# Sheet2.net
KiCad netlist of a schematic drawn in Altium Designer
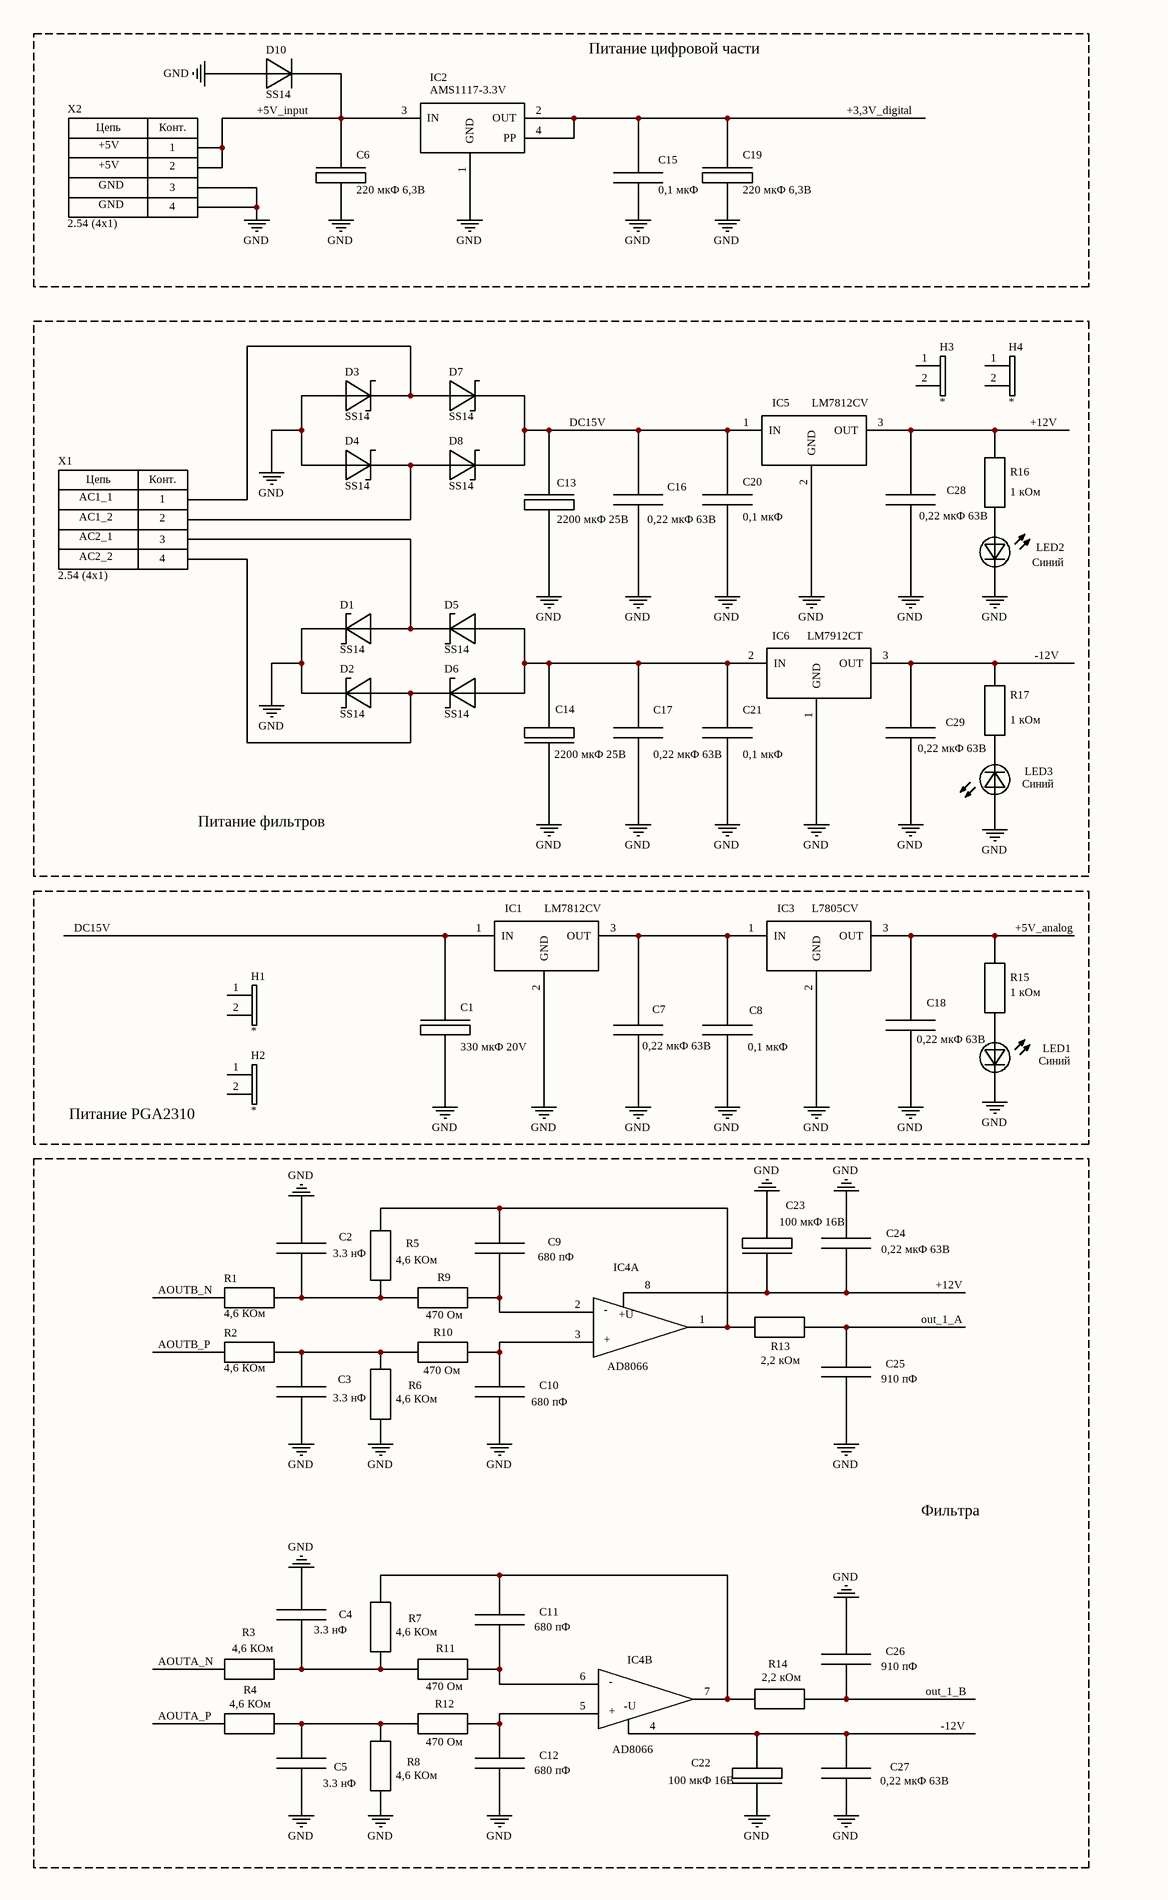
[diagram p0: Sheet2.SchDoc, left]
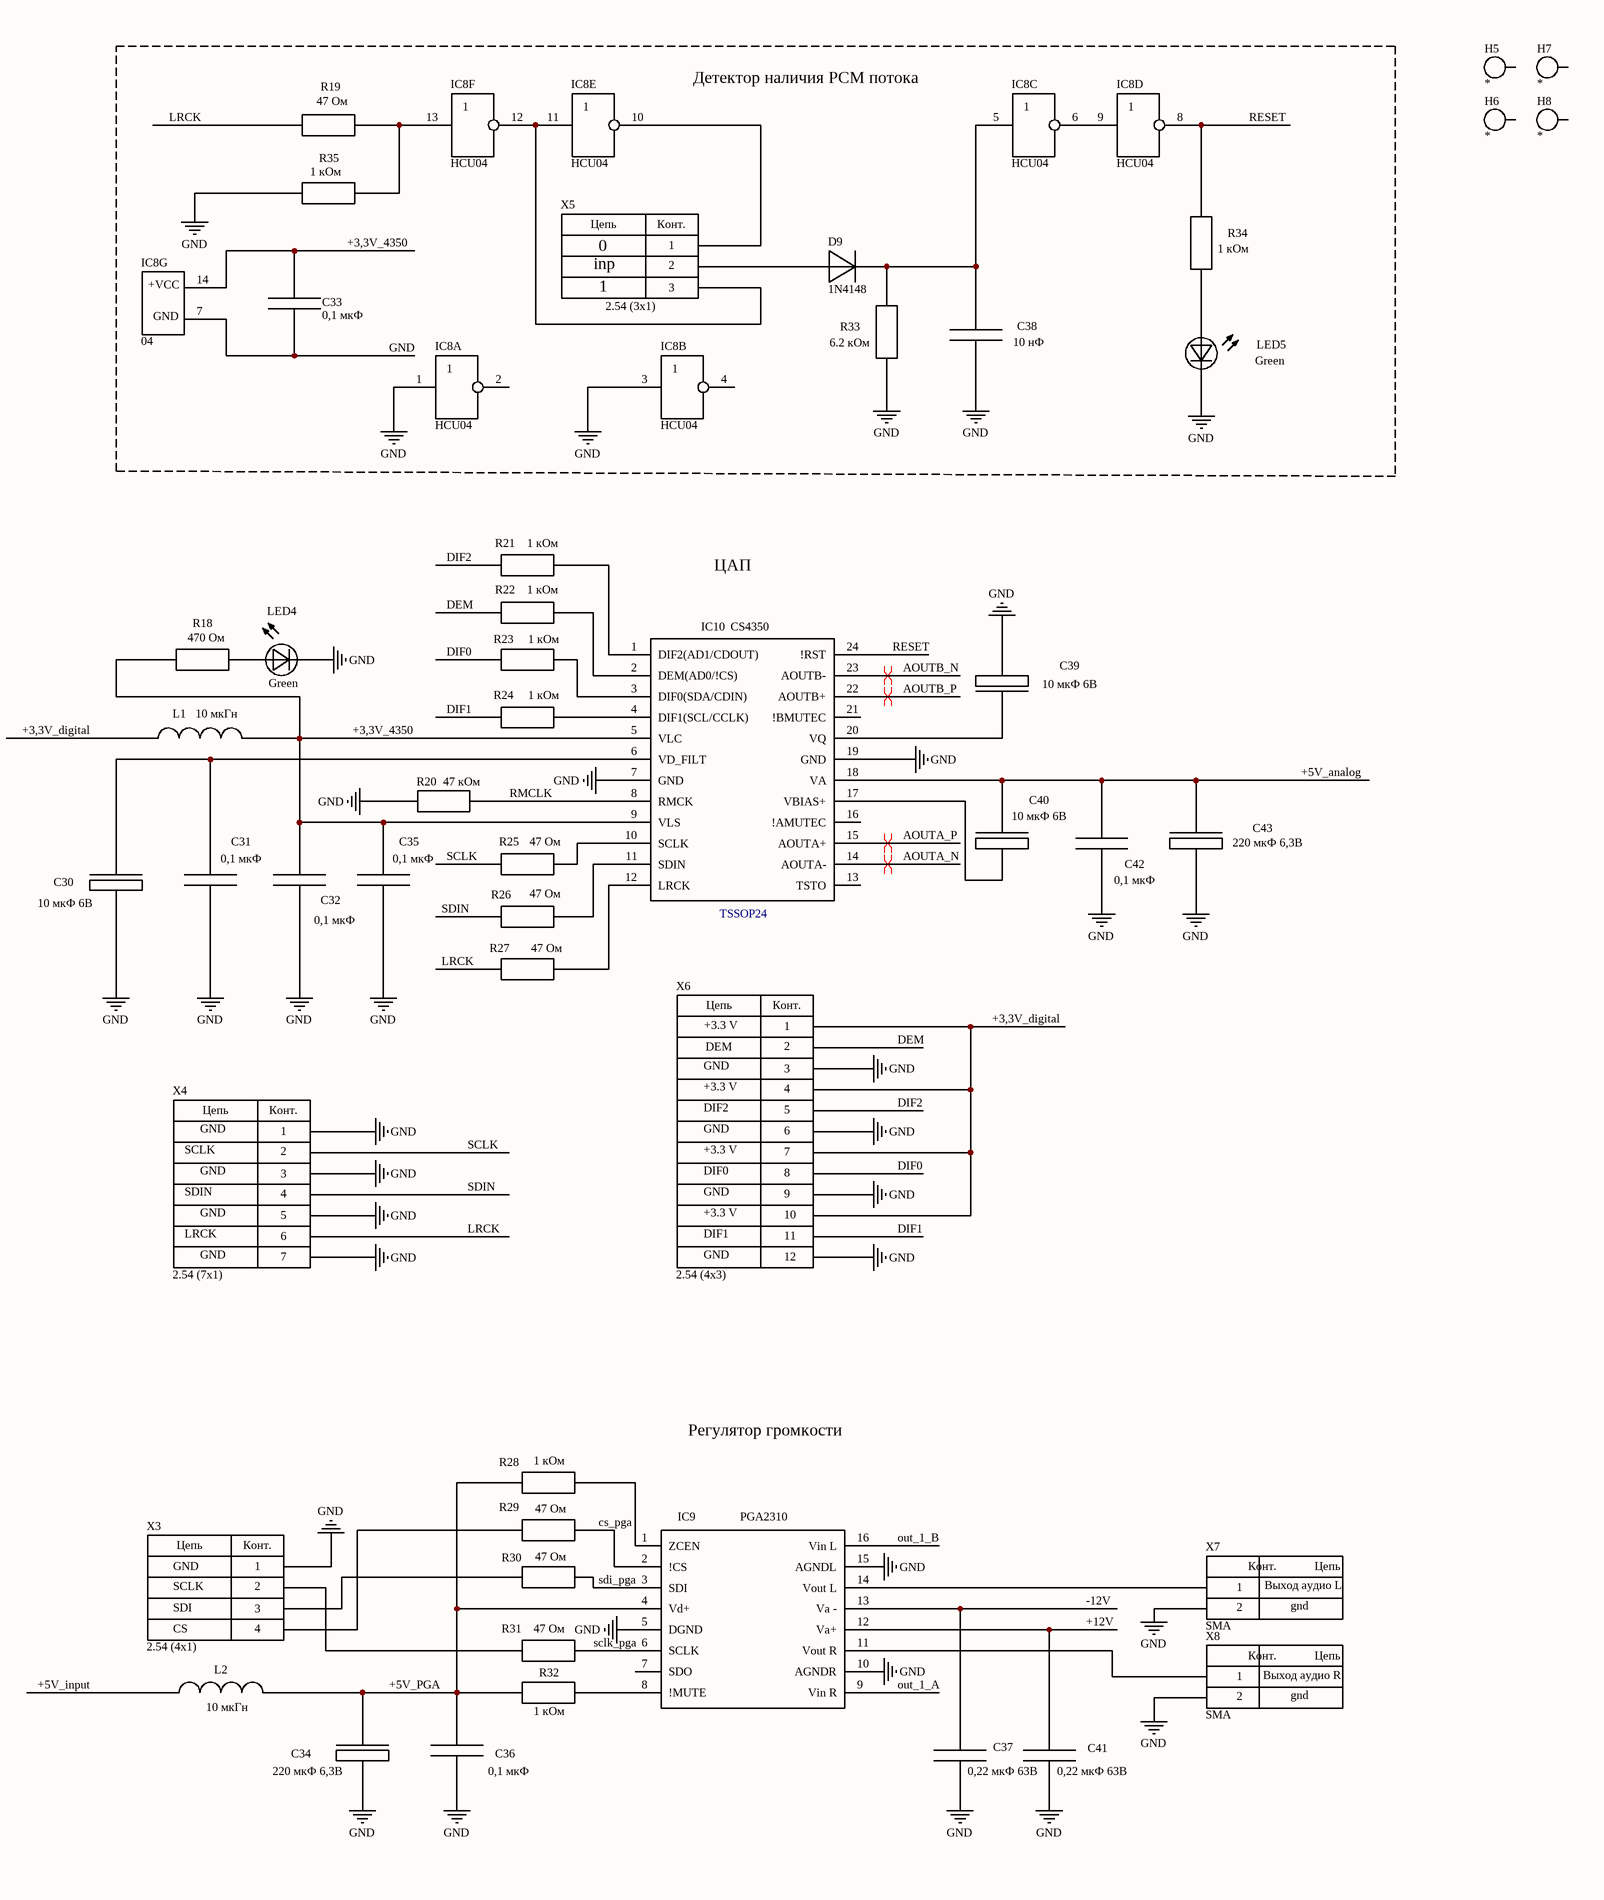
[diagram p1: Sheet2.SchDoc, right]

(export (version "E")
  (design (tool "Eeschema 10.0.6"))
  (components
    (comp (ref "C1")
      (value "330 мкФ 20V")
      (footprint "Конденсатор D=8 H=11.5")
      (libsource (lib "") (part "Конденсатор_1"))
    )
    (comp (ref "C2")
      (value "3.3 нФ")
      (footprint "Конденсатор WIMA 4.5x7x5")
      (libsource (lib "S83") (part "Конденсатор"))
    )
    (comp (ref "C3")
      (value "3.3 нФ")
      (footprint "Конденсатор WIMA 4.5x7x5")
      (libsource (lib "S83") (part "Конденсатор"))
    )
    (comp (ref "C4")
      (value "3.3 нФ")
      (footprint "Конденсатор WIMA 4.5x7x5")
      (libsource (lib "S83") (part "Конденсатор"))
    )
    (comp (ref "C5")
      (value "3.3 нФ")
      (footprint "Конденсатор WIMA 4.5x7x5")
      (libsource (lib "S83") (part "Конденсатор"))
    )
    (comp (ref "C6")
      (value "220 мкФ 6,3В")
      (footprint "Конденсатор SMD Case Size D")
      (libsource (lib "") (part "Конденсатор_1"))
    )
    (comp (ref "C7")
      (value "0,22 мкФ 63В")
      (footprint "Конденсатор WIMA 3x7x7")
      (libsource (lib "S83") (part "Конденсатор"))
    )
    (comp (ref "C8")
      (value "0,1 мкФ")
      (footprint "Конденсатор SMD Case 1206")
      (libsource (lib "S83") (part "Конденсатор"))
    )
    (comp (ref "C9")
      (value "680 пФ")
      (footprint "Конденсатор WIMA 4.5x7x5")
      (libsource (lib "S83") (part "Конденсатор"))
    )
    (comp (ref "C10")
      (value "680 пФ")
      (footprint "Конденсатор WIMA 4.5x7x5")
      (libsource (lib "S83") (part "Конденсатор"))
    )
    (comp (ref "C11")
      (value "680 пФ")
      (footprint "Конденсатор WIMA 4.5x7x5")
      (libsource (lib "S83") (part "Конденсатор"))
    )
    (comp (ref "C12")
      (value "680 пФ")
      (footprint "Конденсатор WIMA 4.5x7x5")
      (libsource (lib "S83") (part "Конденсатор"))
    )
    (comp (ref "C13")
      (value "2200 мкФ 25В")
      (footprint "Конденсатор D=13 H=25")
      (libsource (lib "") (part "Конденсатор_1"))
    )
    (comp (ref "C14")
      (value "2200 мкФ 25В")
      (footprint "Конденсатор D=13 H=25")
      (libsource (lib "") (part "Конденсатор_1"))
    )
    (comp (ref "C15")
      (value "0,1 мкФ")
      (footprint "Конденсатор SMD Case 1206")
      (libsource (lib "S83") (part "Конденсатор"))
    )
    (comp (ref "C16")
      (value "0,22 мкФ 63В")
      (footprint "Конденсатор WIMA 3x7x7")
      (libsource (lib "S83") (part "Конденсатор"))
    )
    (comp (ref "C17")
      (value "0,22 мкФ 63В")
      (footprint "Конденсатор WIMA 3x7x7")
      (libsource (lib "S83") (part "Конденсатор"))
    )
    (comp (ref "C18")
      (value "0,22 мкФ 63В")
      (footprint "Конденсатор WIMA 3x7x7")
      (libsource (lib "S83") (part "Конденсатор"))
    )
    (comp (ref "C19")
      (value "220 мкФ 6,3В")
      (footprint "Конденсатор SMD Case Size D")
      (libsource (lib "") (part "Конденсатор_1"))
    )
    (comp (ref "C20")
      (value "0,1 мкФ")
      (footprint "Конденсатор SMD Case 1206")
      (libsource (lib "S83") (part "Конденсатор"))
    )
    (comp (ref "C21")
      (value "0,1 мкФ")
      (footprint "Конденсатор SMD Case 1206")
      (libsource (lib "S83") (part "Конденсатор"))
    )
    (comp (ref "C22")
      (value "100 мкФ 16В")
      (footprint "Конденсатор SMD Case Size D")
      (libsource (lib "") (part "Конденсатор_1"))
    )
    (comp (ref "C23")
      (value "100 мкФ 16В")
      (footprint "Конденсатор SMD Case Size D")
      (libsource (lib "") (part "Конденсатор_1"))
    )
    (comp (ref "C24")
      (value "0,22 мкФ 63В")
      (footprint "Конденсатор WIMA 3x7x7")
      (libsource (lib "S83") (part "Конденсатор"))
    )
    (comp (ref "C25")
      (value "910 пФ")
      (footprint "Конденсатор WIMA 4.5x7x5")
      (libsource (lib "S83") (part "Конденсатор"))
    )
    (comp (ref "C26")
      (value "910 пФ")
      (footprint "Конденсатор WIMA 4.5x7x5")
      (libsource (lib "S83") (part "Конденсатор"))
    )
    (comp (ref "C27")
      (value "0,22 мкФ 63В")
      (footprint "Конденсатор WIMA 3x7x7")
      (libsource (lib "S83") (part "Конденсатор"))
    )
    (comp (ref "C28")
      (value "0,22 мкФ 63В")
      (footprint "Конденсатор WIMA 3x7x7")
      (libsource (lib "S83") (part "Конденсатор"))
    )
    (comp (ref "C29")
      (value "0,22 мкФ 63В")
      (footprint "Конденсатор WIMA 3x7x7")
      (libsource (lib "S83") (part "Конденсатор"))
    )
    (comp (ref "C30")
      (value "10 мкФ 6В")
      (footprint "Конденсатор SMD Case Size B")
      (libsource (lib "") (part "Конденсатор_1"))
    )
    (comp (ref "C31")
      (value "0,1 мкФ")
      (footprint "Конденсатор SMD Case 1206")
      (libsource (lib "S83") (part "Конденсатор"))
    )
    (comp (ref "C32")
      (value "0,1 мкФ")
      (footprint "Конденсатор SMD Case 1206")
      (libsource (lib "S83") (part "Конденсатор"))
    )
    (comp (ref "C33")
      (value "0,1 мкФ")
      (footprint "Конденсатор SMD Case 1206")
      (libsource (lib "S83") (part "Конденсатор"))
    )
    (comp (ref "C34")
      (value "220 мкФ 6,3В")
      (footprint "Конденсатор SMD Case Size D")
      (libsource (lib "") (part "Конденсатор_1"))
    )
    (comp (ref "C35")
      (value "0,1 мкФ")
      (footprint "Конденсатор SMD Case 1206")
      (libsource (lib "S83") (part "Конденсатор"))
    )
    (comp (ref "C36")
      (value "0,1 мкФ")
      (footprint "Конденсатор SMD Case 1206")
      (libsource (lib "S83") (part "Конденсатор"))
    )
    (comp (ref "C37")
      (value "0,22 мкФ 63В")
      (footprint "Конденсатор WIMA 3x7x7")
      (libsource (lib "S83") (part "Конденсатор"))
    )
    (comp (ref "C38")
      (value "10 нФ")
      (footprint "Конденсатор SMD Case 1206")
      (libsource (lib "S83") (part "Конденсатор"))
    )
    (comp (ref "C39")
      (value "10 мкФ 6В")
      (footprint "Конденсатор SMD Case Size B")
      (libsource (lib "") (part "Конденсатор_1"))
    )
    (comp (ref "C40")
      (value "10 мкФ 6В")
      (footprint "Конденсатор SMD Case Size B")
      (libsource (lib "") (part "Конденсатор_1"))
    )
    (comp (ref "C41")
      (value "0,22 мкФ 63В")
      (footprint "Конденсатор WIMA 3x7x7")
      (libsource (lib "S83") (part "Конденсатор"))
    )
    (comp (ref "C42")
      (value "0,1 мкФ")
      (footprint "Конденсатор SMD Case 1206")
      (libsource (lib "S83") (part "Конденсатор"))
    )
    (comp (ref "C43")
      (value "220 мкФ 6,3В")
      (footprint "Конденсатор SMD Case Size D")
      (libsource (lib "") (part "Конденсатор_1"))
    )
    (comp (ref "D1") (value "SS14") (footprint "Диод SS14") (libsource (lib "S83") (part "Диод")))
    (comp (ref "D2") (value "SS14") (footprint "Диод SS14") (libsource (lib "S83") (part "Диод")))
    (comp (ref "D3") (value "SS14") (footprint "Диод SS14") (libsource (lib "S83") (part "Диод")))
    (comp (ref "D4") (value "SS14") (footprint "Диод SS14") (libsource (lib "S83") (part "Диод")))
    (comp (ref "D5") (value "SS14") (footprint "Диод SS14") (libsource (lib "S83") (part "Диод")))
    (comp (ref "D6") (value "SS14") (footprint "Диод SS14") (libsource (lib "S83") (part "Диод")))
    (comp (ref "D7") (value "SS14") (footprint "Диод SS14") (libsource (lib "S83") (part "Диод")))
    (comp (ref "D8") (value "SS14") (footprint "Диод SS14") (libsource (lib "S83") (part "Диод")))
    (comp (ref "D9") (value "1N4148") (footprint "SMD 1206 Диод") (libsource (lib "") (part "Диод_2")))
    (comp (ref "D10") (value "SS14") (footprint "Диод SS14") (libsource (lib "") (part "Диод_1")))
    (comp (ref "H1") (value "*") (footprint "Радиатор 02 (YA25)") (libsource (lib "S83") (part "Радиатор")))
    (comp (ref "H2") (value "*") (footprint "Радиатор 02 (YA25)") (libsource (lib "S83") (part "Радиатор")))
    (comp (ref "H3") (value "*") (footprint "Радиатор 02 (YA25)") (libsource (lib "S83") (part "Радиатор")))
    (comp (ref "H4") (value "*") (footprint "Радиатор 02 (YA25)") (libsource (lib "S83") (part "Радиатор")))
    (comp (ref "H5")
      (value "*")
      (footprint "Отверстие 3,2")
      (libsource (lib "S83") (part "Отверстие монтажное"))
    )
    (comp (ref "H6")
      (value "*")
      (footprint "Отверстие 3,2")
      (libsource (lib "S83") (part "Отверстие монтажное"))
    )
    (comp (ref "H7")
      (value "*")
      (footprint "Отверстие 3,2")
      (libsource (lib "S83") (part "Отверстие монтажное"))
    )
    (comp (ref "H8")
      (value "*")
      (footprint "Отверстие 3,2")
      (libsource (lib "S83") (part "Отверстие монтажное"))
    )
    (comp (ref "IC1") (value "LM7812CV") (footprint "TO-220") (libsource (lib "S83_IC") (part "LM7805")))
    (comp (ref "IC2")
      (value "AMS1117-3.3V")
      (footprint "SOT-223")
      (libsource (lib "S83_IC") (part "AMS1117"))
    )
    (comp (ref "IC3") (value "L7805CV") (footprint "TO-220") (libsource (lib "S83_IC") (part "LM7805")))
    (comp (ref "IC4") (value "AD8066") (footprint "SO-8") (libsource (lib "S83_IC") (part "AD8066")))
    (comp (ref "IC5") (value "LM7812CV") (footprint "TO-220") (libsource (lib "S83_IC") (part "LM7805")))
    (comp (ref "IC6") (value "LM7912CT") (footprint "TO-220") (libsource (lib "S83_IC") (part "LM7905")))
    (comp (ref "IC8") (value "HCU04") (footprint "SOIC-14") (libsource (lib "S83_IC") (part "IN74AC04D")))
    (comp (ref "IC9") (value "PGA2310") (footprint "SOIC-16_2") (libsource (lib "S83_IC") (part "PGA2310UA")))
    (comp (ref "IC10")
      (value "CS4350")
      (footprint "TSSOP24")
      (fields (field (name "CASE") "TSSOP24"))
      (libsource (lib "S83_IC") (part "CS4350"))
    )
    (comp (ref "L1")
      (value "10 мкГн")
      (footprint "SMD 1206 Индуктивность")
      (libsource (lib "S83_transformers") (part "Inductor 10uH (100)"))
    )
    (comp (ref "L2")
      (value "10 мкГн")
      (footprint "SMD 1206 Индуктивность")
      (libsource (lib "S83_transformers") (part "Inductor 10uH (100)"))
    )
    (comp (ref "LED1")
      (value "Синий")
      (footprint "SMD 1206 Светодиод ВАЙТ")
      (libsource (lib "S83") (part "Светодиод"))
    )
    (comp (ref "LED2")
      (value "Синий")
      (footprint "SMD 1206 Светодиод ВАЙТ")
      (libsource (lib "S83") (part "Светодиод"))
    )
    (comp (ref "LED3")
      (value "Синий")
      (footprint "SMD 1206 Светодиод ВАЙТ")
      (libsource (lib "S83") (part "Светодиод"))
    )
    (comp (ref "LED4")
      (value "Green")
      (footprint "SMD 1206 Светодиод ВАЙТ")
      (libsource (lib "S83") (part "Светодиод"))
    )
    (comp (ref "LED5")
      (value "Green")
      (footprint "SMD 1206 Светодиод ВАЙТ")
      (libsource (lib "S83") (part "Светодиод"))
    )
    (comp (ref "R1")
      (value "4,6 КОм")
      (footprint "SMD 1206 Резистор")
      (libsource (lib "S83") (part "Резистор"))
    )
    (comp (ref "R2")
      (value "4,6 КОм")
      (footprint "SMD 1206 Резистор")
      (libsource (lib "S83") (part "Резистор"))
    )
    (comp (ref "R3")
      (value "4,6 КОм")
      (footprint "SMD 1206 Резистор")
      (libsource (lib "S83") (part "Резистор"))
    )
    (comp (ref "R4")
      (value "4,6 КОм")
      (footprint "SMD 1206 Резистор")
      (libsource (lib "S83") (part "Резистор"))
    )
    (comp (ref "R5")
      (value "4,6 КОм")
      (footprint "SMD 1206 Резистор")
      (libsource (lib "S83") (part "Резистор"))
    )
    (comp (ref "R6")
      (value "4,6 КОм")
      (footprint "SMD 1206 Резистор")
      (libsource (lib "S83") (part "Резистор"))
    )
    (comp (ref "R7")
      (value "4,6 КОм")
      (footprint "SMD 1206 Резистор")
      (libsource (lib "S83") (part "Резистор"))
    )
    (comp (ref "R8")
      (value "4,6 КОм")
      (footprint "SMD 1206 Резистор")
      (libsource (lib "S83") (part "Резистор"))
    )
    (comp (ref "R9")
      (value "470 Ом")
      (footprint "SMD 1206 Резистор")
      (libsource (lib "S83") (part "Резистор"))
    )
    (comp (ref "R10")
      (value "470 Ом")
      (footprint "SMD 1206 Резистор")
      (libsource (lib "S83") (part "Резистор"))
    )
    (comp (ref "R11")
      (value "470 Ом")
      (footprint "SMD 1206 Резистор")
      (libsource (lib "S83") (part "Резистор"))
    )
    (comp (ref "R12")
      (value "470 Ом")
      (footprint "SMD 1206 Резистор")
      (libsource (lib "S83") (part "Резистор"))
    )
    (comp (ref "R13")
      (value "2,2 кОм")
      (footprint "Резистор МЛТ 0,125-0,25Вт")
      (libsource (lib "S83") (part "Резистор"))
    )
    (comp (ref "R14")
      (value "2,2 кОм")
      (footprint "Резистор МЛТ 0,125-0,25Вт")
      (libsource (lib "S83") (part "Резистор"))
    )
    (comp (ref "R15")
      (value "1 кОм")
      (footprint "SMD 1206 Резистор")
      (libsource (lib "S83") (part "Резистор"))
    )
    (comp (ref "R16")
      (value "1 кОм")
      (footprint "SMD 1206 Резистор")
      (libsource (lib "S83") (part "Резистор"))
    )
    (comp (ref "R17")
      (value "1 кОм")
      (footprint "SMD 1206 Резистор")
      (libsource (lib "S83") (part "Резистор"))
    )
    (comp (ref "R18")
      (value "470 Ом")
      (footprint "SMD 1206 Резистор")
      (libsource (lib "S83") (part "Резистор"))
    )
    (comp (ref "R19")
      (value "47 Ом")
      (footprint "SMD 1206 Резистор")
      (libsource (lib "S83") (part "Резистор"))
    )
    (comp (ref "R20")
      (value "47 кОм")
      (footprint "SMD 1206 Резистор")
      (libsource (lib "S83") (part "Резистор"))
    )
    (comp (ref "R21")
      (value "1 кОм")
      (footprint "SMD 1206 Резистор")
      (libsource (lib "S83") (part "Резистор"))
    )
    (comp (ref "R22")
      (value "1 кОм")
      (footprint "SMD 1206 Резистор")
      (libsource (lib "S83") (part "Резистор"))
    )
    (comp (ref "R23")
      (value "1 кОм")
      (footprint "SMD 1206 Резистор")
      (libsource (lib "S83") (part "Резистор"))
    )
    (comp (ref "R24")
      (value "1 кОм")
      (footprint "SMD 1206 Резистор")
      (libsource (lib "S83") (part "Резистор"))
    )
    (comp (ref "R25")
      (value "47 Ом")
      (footprint "SMD 1206 Резистор")
      (libsource (lib "S83") (part "Резистор"))
    )
    (comp (ref "R26")
      (value "47 Ом")
      (footprint "SMD 1206 Резистор")
      (libsource (lib "S83") (part "Резистор"))
    )
    (comp (ref "R27")
      (value "47 Ом")
      (footprint "SMD 1206 Резистор")
      (libsource (lib "S83") (part "Резистор"))
    )
    (comp (ref "R28")
      (value "1 кОм")
      (footprint "SMD 1206 Резистор")
      (libsource (lib "S83") (part "Резистор"))
    )
    (comp (ref "R29")
      (value "47 Ом")
      (footprint "SMD 1206 Резистор")
      (libsource (lib "S83") (part "Резистор"))
    )
    (comp (ref "R30")
      (value "47 Ом")
      (footprint "SMD 1206 Резистор")
      (libsource (lib "S83") (part "Резистор"))
    )
    (comp (ref "R31")
      (value "47 Ом")
      (footprint "SMD 1206 Резистор")
      (libsource (lib "S83") (part "Резистор"))
    )
    (comp (ref "R32")
      (value "1 кОм")
      (footprint "SMD 1206 Резистор")
      (libsource (lib "S83") (part "Резистор"))
    )
    (comp (ref "R33")
      (value "6.2 кОм")
      (footprint "SMD 1206 Резистор")
      (libsource (lib "S83") (part "Резистор"))
    )
    (comp (ref "R34")
      (value "1 кОм")
      (footprint "SMD 1206 Резистор")
      (libsource (lib "S83") (part "Резистор"))
    )
    (comp (ref "R35")
      (value "1 кОм")
      (footprint "SMD 1206 Резистор")
      (libsource (lib "S83") (part "Резистор"))
    )
    (comp (ref "X1")
      (value "2.54 (4x1)")
      (footprint "terminal block 3.81mm 4way")
      (libsource (lib "S83_connectors") (part "Terminal block 3.81mm 4way"))
    )
    (comp (ref "X2")
      (value "2.54 (4x1)")
      (footprint "(1x4)PIN 2.54 HEADR")
      (libsource (lib "S83_connectors") (part "(1x4)pin 2.54 Header"))
    )
    (comp (ref "X3")
      (value "2.54 (4x1)")
      (footprint "(1x4)PIN 2.54 HEADR")
      (libsource (lib "S83_connectors") (part "(1x4)pin 2.54 Header"))
    )
    (comp (ref "X4")
      (value "2.54 (7x1)")
      (footprint "(1x7) PIN 2.54 HEADER")
      (libsource (lib "S83_connectors") (part "(1x7) pin 2.54 Header"))
    )
    (comp (ref "X5")
      (value "2.54 (3x1)")
      (footprint "(1x3)PIN 2.54 header")
      (libsource (lib "S83_connectors") (part "(1x3)pin 2.54 Header"))
    )
    (comp (ref "X6")
      (value "2.54 (4x3)")
      (footprint "(3X4)pin 2.54 HEADER")
      (libsource (lib "S83_connectors") (part "(3x4)pin 2.54 Header"))
    )
    (comp (ref "X7") (value "SMA") (footprint "SMA_01") (libsource (lib "S83_connectors") (part "SMA_01")))
    (comp (ref "X8") (value "SMA") (footprint "SMA_01") (libsource (lib "S83_connectors") (part "SMA_01")))
  )
  (nets
    (net (code "1") (name "/+3,3V_4350") (class "Default")
      (node (ref "C32") (pin "1") (pinfunction "+_1") (pintype "passive"))
      (node (ref "C33") (pin "1") (pinfunction "+_1") (pintype "passive"))
      (node (ref "C35") (pin "1") (pinfunction "+_1") (pintype "passive"))
      (node (ref "IC10") (pin "5") (pinfunction "VLC_5") (pintype "passive"))
      (node (ref "IC10") (pin "9") (pinfunction "VLS_9") (pintype "passive"))
      (node (ref "IC8") (pin "14") (pinfunction "pin_1_14") (pintype "passive"))
      (node (ref "L1") (pin "2") (pinfunction "2_2") (pintype "passive"))
      (node (ref "R18") (pin "2") (pinfunction "right_2") (pintype "passive"))
    )
    (net (code "2") (name "/+3,3V_digital") (class "Default")
      (node (ref "C15") (pin "1") (pinfunction "+_1") (pintype "passive"))
      (node (ref "C19") (pin "1") (pinfunction "1_1") (pintype "passive"))
      (node (ref "IC2") (pin "2") (pinfunction "OUT_2") (pintype "passive"))
      (node (ref "IC2") (pin "4") (pinfunction "PP_4") (pintype "passive"))
      (node (ref "L1") (pin "1") (pinfunction "1_1") (pintype "passive"))
      (node (ref "X6") (pin "1") (pinfunction "1_1") (pintype "passive"))
      (node (ref "X6") (pin "10") (pinfunction "10_10") (pintype "passive"))
      (node (ref "X6") (pin "4") (pinfunction "4_4") (pintype "passive"))
      (node (ref "X6") (pin "7") (pinfunction "7_7") (pintype "passive"))
    )
    (net (code "3") (name "/+5V_PGA") (class "Default")
      (node (ref "C34") (pin "1") (pinfunction "1_1") (pintype "passive"))
      (node (ref "C36") (pin "1") (pinfunction "+_1") (pintype "passive"))
      (node (ref "IC9") (pin "4") (pinfunction "Vd+_4") (pintype "passive"))
      (node (ref "L2") (pin "2") (pinfunction "2_2") (pintype "passive"))
      (node (ref "R28") (pin "1") (pinfunction "left_1") (pintype "passive"))
      (node (ref "R32") (pin "1") (pinfunction "left_1") (pintype "passive"))
    )
    (net (code "4") (name "/+5V_analog") (class "Default")
      (node (ref "C18") (pin "1") (pinfunction "+_1") (pintype "passive"))
      (node (ref "C40") (pin "1") (pinfunction "1_1") (pintype "passive"))
      (node (ref "C42") (pin "1") (pinfunction "+_1") (pintype "passive"))
      (node (ref "C43") (pin "1") (pinfunction "1_1") (pintype "passive"))
      (node (ref "IC10") (pin "18") (pinfunction "VA_18") (pintype "passive"))
      (node (ref "IC3") (pin "3") (pinfunction "OUT_3") (pintype "passive"))
      (node (ref "R15") (pin "2") (pinfunction "right_2") (pintype "passive"))
    )
    (net (code "5") (name "/+5V_input") (class "Default")
      (node (ref "C6") (pin "1") (pinfunction "1_1") (pintype "passive"))
      (node (ref "D10") (pin "2") (pinfunction "K_2") (pintype "passive"))
      (node (ref "IC2") (pin "3") (pinfunction "IN_3") (pintype "passive"))
      (node (ref "L2") (pin "1") (pinfunction "1_1") (pintype "passive"))
      (node (ref "X2") (pin "1") (pinfunction "1_1") (pintype "passive"))
      (node (ref "X2") (pin "2") (pinfunction "2_2") (pintype "passive"))
    )
    (net (code "6") (name "/+12V") (class "Default")
      (node (ref "C23") (pin "1") (pinfunction "1_1") (pintype "passive"))
      (node (ref "C24") (pin "1") (pinfunction "+_1") (pintype "passive"))
      (node (ref "C28") (pin "1") (pinfunction "+_1") (pintype "passive"))
      (node (ref "C41") (pin "1") (pinfunction "+_1") (pintype "passive"))
      (node (ref "IC4") (pin "8") (pinfunction "pin_8_8") (pintype "passive"))
      (node (ref "IC5") (pin "3") (pinfunction "OUT_3") (pintype "passive"))
      (node (ref "IC9") (pin "12") (pinfunction "Va+_12") (pintype "passive"))
      (node (ref "R16") (pin "2") (pinfunction "right_2") (pintype "passive"))
    )
    (net (code "7") (name "/-12V") (class "Default")
      (node (ref "C22") (pin "2") (pinfunction "2_2") (pintype "passive"))
      (node (ref "C27") (pin "1") (pinfunction "+_1") (pintype "passive"))
      (node (ref "C29") (pin "1") (pinfunction "+_1") (pintype "passive"))
      (node (ref "C37") (pin "1") (pinfunction "+_1") (pintype "passive"))
      (node (ref "IC4") (pin "4") (pinfunction "pin_4_4") (pintype "passive"))
      (node (ref "IC6") (pin "3") (pinfunction "OUT_3") (pintype "passive"))
      (node (ref "IC9") (pin "13") (pinfunction "Va_-_13") (pintype "passive"))
      (node (ref "R17") (pin "2") (pinfunction "right_2") (pintype "passive"))
    )
    (net (code "8") (name "/AOUTA_N") (class "Default")
      (node (ref "IC10") (pin "14") (pinfunction "AOUTA-_14") (pintype "passive"))
      (node (ref "R3") (pin "1") (pinfunction "left_1") (pintype "passive"))
    )
    (net (code "9") (name "/AOUTA_P") (class "Default")
      (node (ref "IC10") (pin "15") (pinfunction "AOUTA+_15") (pintype "passive"))
      (node (ref "R4") (pin "1") (pinfunction "left_1") (pintype "passive"))
    )
    (net (code "10") (name "/AOUTB_N") (class "Default")
      (node (ref "IC10") (pin "23") (pinfunction "AOUTB-_23") (pintype "passive"))
      (node (ref "R1") (pin "1") (pinfunction "left_1") (pintype "passive"))
    )
    (net (code "11") (name "/AOUTB_P") (class "Default")
      (node (ref "IC10") (pin "22") (pinfunction "AOUTB+_22") (pintype "passive"))
      (node (ref "R2") (pin "1") (pinfunction "left_1") (pintype "passive"))
    )
    (net (code "12") (name "/DC15V") (class "Default")
      (node (ref "C1") (pin "1") (pinfunction "1_1") (pintype "passive"))
      (node (ref "C13") (pin "1") (pinfunction "1_1") (pintype "passive"))
      (node (ref "C16") (pin "1") (pinfunction "+_1") (pintype "passive"))
      (node (ref "C20") (pin "1") (pinfunction "+_1") (pintype "passive"))
      (node (ref "D7") (pin "2") (pinfunction "K_2") (pintype "passive"))
      (node (ref "D8") (pin "2") (pinfunction "K_2") (pintype "passive"))
      (node (ref "IC1") (pin "1") (pinfunction "IN_1") (pintype "passive"))
      (node (ref "IC5") (pin "1") (pinfunction "IN_1") (pintype "passive"))
    )
    (net (code "13") (name "/DEM") (class "Default")
      (node (ref "R22") (pin "1") (pinfunction "left_1") (pintype "passive"))
      (node (ref "X6") (pin "2") (pinfunction "2_2") (pintype "passive"))
    )
    (net (code "14") (name "/DIF0") (class "Default")
      (node (ref "R23") (pin "1") (pinfunction "left_1") (pintype "passive"))
      (node (ref "X6") (pin "8") (pinfunction "8_8") (pintype "passive"))
    )
    (net (code "15") (name "/DIF1") (class "Default")
      (node (ref "R24") (pin "1") (pinfunction "left_1") (pintype "passive"))
      (node (ref "X6") (pin "11") (pinfunction "11_11") (pintype "passive"))
    )
    (net (code "16") (name "/DIF2") (class "Default")
      (node (ref "R21") (pin "1") (pinfunction "left_1") (pintype "passive"))
      (node (ref "X6") (pin "5") (pinfunction "5_5") (pintype "passive"))
    )
    (net (code "17") (name "/LRCK") (class "Default")
      (node (ref "R19") (pin "2") (pinfunction "right_2") (pintype "passive"))
      (node (ref "R27") (pin "1") (pinfunction "left_1") (pintype "passive"))
      (node (ref "X4") (pin "6") (pinfunction "6_6") (pintype "passive"))
    )
    (net (code "18") (name "/RESET") (class "Default")
      (node (ref "IC10") (pin "24") (pinfunction "!RST_24") (pintype "passive"))
      (node (ref "IC8") (pin "8") (pinfunction "pin_2_8") (pintype "passive"))
      (node (ref "R34") (pin "2") (pinfunction "right_2") (pintype "passive"))
    )
    (net (code "19") (name "/RMCLK") (class "Default")
      (node (ref "IC10") (pin "8") (pinfunction "RMCK_8") (pintype "passive"))
      (node (ref "R20") (pin "2") (pinfunction "right_2") (pintype "passive"))
    )
    (net (code "20") (name "/SCLK") (class "Default")
      (node (ref "R25") (pin "1") (pinfunction "left_1") (pintype "passive"))
      (node (ref "X4") (pin "2") (pinfunction "2_2") (pintype "passive"))
    )
    (net (code "21") (name "/SDIN") (class "Default")
      (node (ref "R26") (pin "1") (pinfunction "left_1") (pintype "passive"))
      (node (ref "X4") (pin "4") (pinfunction "4_4") (pintype "passive"))
    )
    (net (code "22") (name "/cs_pga") (class "Default")
      (node (ref "IC9") (pin "2") (pinfunction "!CS_2") (pintype "passive"))
      (node (ref "R29") (pin "2") (pinfunction "right_2") (pintype "passive"))
    )
    (net (code "23") (name "/out_1_A") (class "Default")
      (node (ref "C25") (pin "1") (pinfunction "+_1") (pintype "passive"))
      (node (ref "IC9") (pin "9") (pinfunction "Vin_R_9") (pintype "passive"))
      (node (ref "R13") (pin "2") (pinfunction "right_2") (pintype "passive"))
    )
    (net (code "24") (name "/out_1_B") (class "Default")
      (node (ref "C26") (pin "2") (pinfunction "-_2") (pintype "passive"))
      (node (ref "IC9") (pin "16") (pinfunction "Vin_L_16") (pintype "passive"))
      (node (ref "R14") (pin "2") (pinfunction "right_2") (pintype "passive"))
    )
    (net (code "25") (name "/sclk_pga") (class "Default")
      (node (ref "IC9") (pin "6") (pinfunction "SCLK_6") (pintype "passive"))
      (node (ref "R31") (pin "2") (pinfunction "right_2") (pintype "passive"))
    )
    (net (code "26") (name "/sdi_pga") (class "Default")
      (node (ref "IC9") (pin "3") (pinfunction "SDI_3") (pintype "passive"))
      (node (ref "R30") (pin "2") (pinfunction "right_2") (pintype "passive"))
    )
    (net (code "27") (name "GND") (class "Default")
      (node (ref "C1") (pin "2") (pinfunction "2_2") (pintype "passive"))
      (node (ref "C10") (pin "2") (pinfunction "-_2") (pintype "passive"))
      (node (ref "C12") (pin "2") (pinfunction "-_2") (pintype "passive"))
      (node (ref "C13") (pin "2") (pinfunction "2_2") (pintype "passive"))
      (node (ref "C14") (pin "1") (pinfunction "1_1") (pintype "passive"))
      (node (ref "C15") (pin "2") (pinfunction "-_2") (pintype "passive"))
      (node (ref "C16") (pin "2") (pinfunction "-_2") (pintype "passive"))
      (node (ref "C17") (pin "2") (pinfunction "-_2") (pintype "passive"))
      (node (ref "C18") (pin "2") (pinfunction "-_2") (pintype "passive"))
      (node (ref "C19") (pin "2") (pinfunction "2_2") (pintype "passive"))
      (node (ref "C2") (pin "1") (pinfunction "+_1") (pintype "passive"))
      (node (ref "C20") (pin "2") (pinfunction "-_2") (pintype "passive"))
      (node (ref "C21") (pin "2") (pinfunction "-_2") (pintype "passive"))
      (node (ref "C22") (pin "1") (pinfunction "1_1") (pintype "passive"))
      (node (ref "C23") (pin "2") (pinfunction "2_2") (pintype "passive"))
      (node (ref "C24") (pin "2") (pinfunction "-_2") (pintype "passive"))
      (node (ref "C25") (pin "2") (pinfunction "-_2") (pintype "passive"))
      (node (ref "C26") (pin "1") (pinfunction "+_1") (pintype "passive"))
      (node (ref "C27") (pin "2") (pinfunction "-_2") (pintype "passive"))
      (node (ref "C28") (pin "2") (pinfunction "-_2") (pintype "passive"))
      (node (ref "C29") (pin "2") (pinfunction "-_2") (pintype "passive"))
      (node (ref "C3") (pin "2") (pinfunction "-_2") (pintype "passive"))
      (node (ref "C30") (pin "2") (pinfunction "2_2") (pintype "passive"))
      (node (ref "C31") (pin "2") (pinfunction "-_2") (pintype "passive"))
      (node (ref "C32") (pin "2") (pinfunction "-_2") (pintype "passive"))
      (node (ref "C33") (pin "2") (pinfunction "-_2") (pintype "passive"))
      (node (ref "C34") (pin "2") (pinfunction "2_2") (pintype "passive"))
      (node (ref "C35") (pin "2") (pinfunction "-_2") (pintype "passive"))
      (node (ref "C36") (pin "2") (pinfunction "-_2") (pintype "passive"))
      (node (ref "C37") (pin "2") (pinfunction "-_2") (pintype "passive"))
      (node (ref "C38") (pin "2") (pinfunction "-_2") (pintype "passive"))
      (node (ref "C39") (pin "2") (pinfunction "2_2") (pintype "passive"))
      (node (ref "C4") (pin "1") (pinfunction "+_1") (pintype "passive"))
      (node (ref "C41") (pin "2") (pinfunction "-_2") (pintype "passive"))
      (node (ref "C42") (pin "2") (pinfunction "-_2") (pintype "passive"))
      (node (ref "C43") (pin "2") (pinfunction "2_2") (pintype "passive"))
      (node (ref "C5") (pin "2") (pinfunction "-_2") (pintype "passive"))
      (node (ref "C6") (pin "2") (pinfunction "2_2") (pintype "passive"))
      (node (ref "C7") (pin "2") (pinfunction "-_2") (pintype "passive"))
      (node (ref "C8") (pin "2") (pinfunction "-_2") (pintype "passive"))
      (node (ref "D1") (pin "2") (pinfunction "K_2") (pintype "passive"))
      (node (ref "D10") (pin "1") (pinfunction "А_1") (pintype "passive"))
      (node (ref "D2") (pin "2") (pinfunction "K_2") (pintype "passive"))
      (node (ref "D3") (pin "1") (pinfunction "А_1") (pintype "passive"))
      (node (ref "D4") (pin "1") (pinfunction "А_1") (pintype "passive"))
      (node (ref "IC1") (pin "2") (pinfunction "GND_2") (pintype "passive"))
      (node (ref "IC10") (pin "19") (pinfunction "GND_19") (pintype "passive"))
      (node (ref "IC10") (pin "7") (pinfunction "GND_7") (pintype "passive"))
      (node (ref "IC2") (pin "1") (pinfunction "GND_1") (pintype "passive"))
      (node (ref "IC3") (pin "2") (pinfunction "GND_2") (pintype "passive"))
      (node (ref "IC5") (pin "2") (pinfunction "GND_2") (pintype "passive"))
      (node (ref "IC6") (pin "1") (pinfunction "GND_1") (pintype "passive"))
      (node (ref "IC8") (pin "1") (pinfunction "pin_1_1") (pintype "passive"))
      (node (ref "IC8") (pin "3") (pinfunction "pin_1_3") (pintype "passive"))
      (node (ref "IC8") (pin "7") (pinfunction "pin_2_7") (pintype "passive"))
      (node (ref "IC9") (pin "10") (pinfunction "AGNDR_10") (pintype "passive"))
      (node (ref "IC9") (pin "15") (pinfunction "AGNDL_15") (pintype "passive"))
      (node (ref "IC9") (pin "5") (pinfunction "DGND_5") (pintype "passive"))
      (node (ref "LED1") (pin "2") (pinfunction "K_2") (pintype "passive"))
      (node (ref "LED2") (pin "2") (pinfunction "K_2") (pintype "passive"))
      (node (ref "LED3") (pin "1") (pinfunction "А_1") (pintype "passive"))
      (node (ref "LED4") (pin "2") (pinfunction "K_2") (pintype "passive"))
      (node (ref "LED5") (pin "2") (pinfunction "K_2") (pintype "passive"))
      (node (ref "R20") (pin "1") (pinfunction "left_1") (pintype "passive"))
      (node (ref "R33") (pin "1") (pinfunction "left_1") (pintype "passive"))
      (node (ref "R35") (pin "2") (pinfunction "right_2") (pintype "passive"))
      (node (ref "R6") (pin "1") (pinfunction "left_1") (pintype "passive"))
      (node (ref "R8") (pin "1") (pinfunction "left_1") (pintype "passive"))
      (node (ref "X2") (pin "3") (pinfunction "3_3") (pintype "passive"))
      (node (ref "X2") (pin "4") (pinfunction "4_4") (pintype "passive"))
      (node (ref "X3") (pin "1") (pinfunction "1_1") (pintype "passive"))
      (node (ref "X4") (pin "1") (pinfunction "1_1") (pintype "passive"))
      (node (ref "X4") (pin "3") (pinfunction "3_3") (pintype "passive"))
      (node (ref "X4") (pin "5") (pinfunction "5_5") (pintype "passive"))
      (node (ref "X4") (pin "7") (pinfunction "7_7") (pintype "passive"))
      (node (ref "X6") (pin "12") (pinfunction "12_12") (pintype "passive"))
      (node (ref "X6") (pin "3") (pinfunction "3_3") (pintype "passive"))
      (node (ref "X6") (pin "6") (pinfunction "6_6") (pintype "passive"))
      (node (ref "X6") (pin "9") (pinfunction "9_9") (pintype "passive"))
      (node (ref "X7") (pin "2") (pinfunction "2_2") (pintype "passive"))
      (node (ref "X8") (pin "2") (pinfunction "2_2") (pintype "passive"))
    )
    (net (code "28") (name "Net-(C2--)") (class "Default")
      (node (ref "C2") (pin "2") (pinfunction "-_2") (pintype "passive"))
      (node (ref "R1") (pin "2") (pinfunction "right_2") (pintype "passive"))
      (node (ref "R5") (pin "1") (pinfunction "left_1") (pintype "passive"))
      (node (ref "R9") (pin "1") (pinfunction "left_1") (pintype "passive"))
    )
    (net (code "29") (name "Net-(C3-+)") (class "Default")
      (node (ref "C3") (pin "1") (pinfunction "+_1") (pintype "passive"))
      (node (ref "R10") (pin "1") (pinfunction "left_1") (pintype "passive"))
      (node (ref "R2") (pin "2") (pinfunction "right_2") (pintype "passive"))
      (node (ref "R6") (pin "2") (pinfunction "right_2") (pintype "passive"))
    )
    (net (code "30") (name "Net-(C4--)") (class "Default")
      (node (ref "C4") (pin "2") (pinfunction "-_2") (pintype "passive"))
      (node (ref "R11") (pin "1") (pinfunction "left_1") (pintype "passive"))
      (node (ref "R3") (pin "2") (pinfunction "right_2") (pintype "passive"))
      (node (ref "R7") (pin "1") (pinfunction "left_1") (pintype "passive"))
    )
    (net (code "31") (name "Net-(C5-+)") (class "Default")
      (node (ref "C5") (pin "1") (pinfunction "+_1") (pintype "passive"))
      (node (ref "R12") (pin "1") (pinfunction "left_1") (pintype "passive"))
      (node (ref "R4") (pin "2") (pinfunction "right_2") (pintype "passive"))
      (node (ref "R8") (pin "2") (pinfunction "right_2") (pintype "passive"))
    )
    (net (code "32") (name "Net-(C7-+)") (class "Default")
      (node (ref "C7") (pin "1") (pinfunction "+_1") (pintype "passive"))
      (node (ref "C8") (pin "1") (pinfunction "+_1") (pintype "passive"))
      (node (ref "IC1") (pin "3") (pinfunction "OUT_3") (pintype "passive"))
      (node (ref "IC3") (pin "1") (pinfunction "IN_1") (pintype "passive"))
    )
    (net (code "33") (name "Net-(C9-+)") (class "Default")
      (node (ref "C9") (pin "1") (pinfunction "+_1") (pintype "passive"))
      (node (ref "IC4") (pin "1") (pinfunction "pin_1_1") (pintype "passive"))
      (node (ref "R13") (pin "1") (pinfunction "left_1") (pintype "passive"))
      (node (ref "R5") (pin "2") (pinfunction "right_2") (pintype "passive"))
    )
    (net (code "34") (name "Net-(C9--)") (class "Default")
      (node (ref "C9") (pin "2") (pinfunction "-_2") (pintype "passive"))
      (node (ref "IC4") (pin "2") (pinfunction "pin_2_2") (pintype "passive"))
      (node (ref "R9") (pin "2") (pinfunction "right_2") (pintype "passive"))
    )
    (net (code "35") (name "Net-(C10-+)") (class "Default")
      (node (ref "C10") (pin "1") (pinfunction "+_1") (pintype "passive"))
      (node (ref "IC4") (pin "3") (pinfunction "pin_3_3") (pintype "passive"))
      (node (ref "R10") (pin "2") (pinfunction "right_2") (pintype "passive"))
    )
    (net (code "36") (name "Net-(C11-+)") (class "Default")
      (node (ref "C11") (pin "1") (pinfunction "+_1") (pintype "passive"))
      (node (ref "IC4") (pin "7") (pinfunction "pin_7_7") (pintype "passive"))
      (node (ref "R14") (pin "1") (pinfunction "left_1") (pintype "passive"))
      (node (ref "R7") (pin "2") (pinfunction "right_2") (pintype "passive"))
    )
    (net (code "37") (name "Net-(C11--)") (class "Default")
      (node (ref "C11") (pin "2") (pinfunction "-_2") (pintype "passive"))
      (node (ref "IC4") (pin "6") (pinfunction "pin_6_6") (pintype "passive"))
      (node (ref "R11") (pin "2") (pinfunction "right_2") (pintype "passive"))
    )
    (net (code "38") (name "Net-(C12-+)") (class "Default")
      (node (ref "C12") (pin "1") (pinfunction "+_1") (pintype "passive"))
      (node (ref "IC4") (pin "5") (pinfunction "pin_5_5") (pintype "passive"))
      (node (ref "R12") (pin "2") (pinfunction "right_2") (pintype "passive"))
    )
    (net (code "39") (name "Net-(C17-+)") (class "Default")
      (node (ref "C14") (pin "2") (pinfunction "2_2") (pintype "passive"))
      (node (ref "C17") (pin "1") (pinfunction "+_1") (pintype "passive"))
      (node (ref "C21") (pin "1") (pinfunction "+_1") (pintype "passive"))
      (node (ref "D5") (pin "1") (pinfunction "А_1") (pintype "passive"))
      (node (ref "D6") (pin "1") (pinfunction "А_1") (pintype "passive"))
      (node (ref "IC6") (pin "2") (pinfunction "IN_2") (pintype "passive"))
    )
    (net (code "40") (name "Net-(C31-+)") (class "Default")
      (node (ref "C30") (pin "1") (pinfunction "1_1") (pintype "passive"))
      (node (ref "C31") (pin "1") (pinfunction "+_1") (pintype "passive"))
      (node (ref "IC10") (pin "6") (pinfunction "VD_FILT_6") (pintype "passive"))
    )
    (net (code "41") (name "Net-(C38-+)") (class "Default")
      (node (ref "C38") (pin "1") (pinfunction "+_1") (pintype "passive"))
      (node (ref "D9") (pin "2") (pinfunction "K_2") (pintype "passive"))
      (node (ref "IC8") (pin "5") (pinfunction "pin_1_5") (pintype "passive"))
      (node (ref "R33") (pin "2") (pinfunction "right_2") (pintype "passive"))
    )
    (net (code "42") (name "Net-(D1-А)") (class "Default")
      (node (ref "D1") (pin "1") (pinfunction "А_1") (pintype "passive"))
      (node (ref "D5") (pin "2") (pinfunction "K_2") (pintype "passive"))
      (node (ref "X1") (pin "3") (pinfunction "3_3") (pintype "passive"))
    )
    (net (code "43") (name "Net-(D2-А)") (class "Default")
      (node (ref "D2") (pin "1") (pinfunction "А_1") (pintype "passive"))
      (node (ref "D6") (pin "2") (pinfunction "K_2") (pintype "passive"))
      (node (ref "X1") (pin "4") (pinfunction "4_4") (pintype "passive"))
    )
    (net (code "44") (name "Net-(D3-K)") (class "Default")
      (node (ref "D3") (pin "2") (pinfunction "K_2") (pintype "passive"))
      (node (ref "D7") (pin "1") (pinfunction "А_1") (pintype "passive"))
      (node (ref "X1") (pin "1") (pinfunction "1_1") (pintype "passive"))
    )
    (net (code "45") (name "Net-(D4-K)") (class "Default")
      (node (ref "D4") (pin "2") (pinfunction "K_2") (pintype "passive"))
      (node (ref "D8") (pin "1") (pinfunction "А_1") (pintype "passive"))
      (node (ref "X1") (pin "2") (pinfunction "2_2") (pintype "passive"))
    )
    (net (code "46") (name "Net-(D9-А)") (class "Default")
      (node (ref "D9") (pin "1") (pinfunction "А_1") (pintype "passive"))
      (node (ref "X5") (pin "2") (pinfunction "2_2") (pintype "passive"))
    )
    (net (code "47") (name "Net-(IC8C-pin_2)") (class "Default")
      (node (ref "IC8") (pin "6") (pinfunction "pin_2_6") (pintype "passive"))
      (node (ref "IC8") (pin "9") (pinfunction "pin_1_9") (pintype "passive"))
    )
    (net (code "48") (name "Net-(IC8E-pin_1)") (class "Default")
      (node (ref "IC8") (pin "11") (pinfunction "pin_1_11") (pintype "passive"))
      (node (ref "IC8") (pin "12") (pinfunction "pin_2_12") (pintype "passive"))
      (node (ref "X5") (pin "3") (pinfunction "3_3") (pintype "passive"))
    )
    (net (code "49") (name "Net-(IC8E-pin_2)") (class "Default")
      (node (ref "IC8") (pin "10") (pinfunction "pin_2_10") (pintype "passive"))
      (node (ref "X5") (pin "1") (pinfunction "1_1") (pintype "passive"))
    )
    (net (code "50") (name "Net-(IC8F-pin_1)") (class "Default")
      (node (ref "IC8") (pin "13") (pinfunction "pin_1_13") (pintype "passive"))
      (node (ref "R19") (pin "1") (pinfunction "left_1") (pintype "passive"))
      (node (ref "R35") (pin "1") (pinfunction "left_1") (pintype "passive"))
    )
    (net (code "51") (name "Net-(IC9-!MUTE)") (class "Default")
      (node (ref "IC9") (pin "8") (pinfunction "!MUTE_8") (pintype "passive"))
      (node (ref "R32") (pin "2") (pinfunction "right_2") (pintype "passive"))
    )
    (net (code "52") (name "Net-(IC9-Vout_L)") (class "Default")
      (node (ref "IC9") (pin "14") (pinfunction "Vout_L_14") (pintype "passive"))
      (node (ref "X7") (pin "1") (pinfunction "1_1") (pintype "passive"))
    )
    (net (code "53") (name "Net-(IC9-Vout_R)") (class "Default")
      (node (ref "IC9") (pin "11") (pinfunction "Vout_R_11") (pintype "passive"))
      (node (ref "X8") (pin "1") (pinfunction "1_1") (pintype "passive"))
    )
    (net (code "54") (name "Net-(IC9-ZCEN)") (class "Default")
      (node (ref "IC9") (pin "1") (pinfunction "ZCEN_1") (pintype "passive"))
      (node (ref "R28") (pin "2") (pinfunction "right_2") (pintype "passive"))
    )
    (net (code "55") (name "Net-(IC10-DEM(AD0{slash}!CS))") (class "Default")
      (node (ref "IC10") (pin "2") (pinfunction "DEM(AD0/!CS)_2") (pintype "passive"))
      (node (ref "R22") (pin "2") (pinfunction "right_2") (pintype "passive"))
    )
    (net (code "56") (name "Net-(IC10-DIF0(SDA{slash}CDIN))") (class "Default")
      (node (ref "IC10") (pin "3") (pinfunction "DIF0(SDA/CDIN)_3") (pintype "passive"))
      (node (ref "R23") (pin "2") (pinfunction "right_2") (pintype "passive"))
    )
    (net (code "57") (name "Net-(IC10-DIF1(SCL{slash}CCLK))") (class "Default")
      (node (ref "IC10") (pin "4") (pinfunction "DIF1(SCL/CCLK)_4") (pintype "passive"))
      (node (ref "R24") (pin "2") (pinfunction "right_2") (pintype "passive"))
    )
    (net (code "58") (name "Net-(IC10-DIF2(AD1{slash}CDOUT))") (class "Default")
      (node (ref "IC10") (pin "1") (pinfunction "DIF2(AD1/CDOUT)_1") (pintype "passive"))
      (node (ref "R21") (pin "2") (pinfunction "right_2") (pintype "passive"))
    )
    (net (code "59") (name "Net-(IC10-LRCK)") (class "Default")
      (node (ref "IC10") (pin "12") (pinfunction "LRCK_12") (pintype "passive"))
      (node (ref "R27") (pin "2") (pinfunction "right_2") (pintype "passive"))
    )
    (net (code "60") (name "Net-(IC10-SCLK)") (class "Default")
      (node (ref "IC10") (pin "10") (pinfunction "SCLK_10") (pintype "passive"))
      (node (ref "R25") (pin "2") (pinfunction "right_2") (pintype "passive"))
    )
    (net (code "61") (name "Net-(IC10-SDIN)") (class "Default")
      (node (ref "IC10") (pin "11") (pinfunction "SDIN_11") (pintype "passive"))
      (node (ref "R26") (pin "2") (pinfunction "right_2") (pintype "passive"))
    )
    (net (code "62") (name "Net-(IC10-VBIAS+)") (class "Default")
      (node (ref "C40") (pin "2") (pinfunction "2_2") (pintype "passive"))
      (node (ref "IC10") (pin "17") (pinfunction "VBIAS+_17") (pintype "passive"))
    )
    (net (code "63") (name "Net-(IC10-VQ)") (class "Default")
      (node (ref "C39") (pin "1") (pinfunction "1_1") (pintype "passive"))
      (node (ref "IC10") (pin "20") (pinfunction "VQ_20") (pintype "passive"))
    )
    (net (code "64") (name "Net-(LED1-А)") (class "Default")
      (node (ref "LED1") (pin "1") (pinfunction "А_1") (pintype "passive"))
      (node (ref "R15") (pin "1") (pinfunction "left_1") (pintype "passive"))
    )
    (net (code "65") (name "Net-(LED2-А)") (class "Default")
      (node (ref "LED2") (pin "1") (pinfunction "А_1") (pintype "passive"))
      (node (ref "R16") (pin "1") (pinfunction "left_1") (pintype "passive"))
    )
    (net (code "66") (name "Net-(LED3-K)") (class "Default")
      (node (ref "LED3") (pin "2") (pinfunction "K_2") (pintype "passive"))
      (node (ref "R17") (pin "1") (pinfunction "left_1") (pintype "passive"))
    )
    (net (code "67") (name "Net-(LED4-А)") (class "Default")
      (node (ref "LED4") (pin "1") (pinfunction "А_1") (pintype "passive"))
      (node (ref "R18") (pin "1") (pinfunction "left_1") (pintype "passive"))
    )
    (net (code "68") (name "Net-(LED5-А)") (class "Default")
      (node (ref "LED5") (pin "1") (pinfunction "А_1") (pintype "passive"))
      (node (ref "R34") (pin "1") (pinfunction "left_1") (pintype "passive"))
    )
    (net (code "69") (name "Net-(R29-left)") (class "Default")
      (node (ref "R29") (pin "1") (pinfunction "left_1") (pintype "passive"))
      (node (ref "X3") (pin "4") (pinfunction "4_4") (pintype "passive"))
    )
    (net (code "70") (name "Net-(R30-left)") (class "Default")
      (node (ref "R30") (pin "1") (pinfunction "left_1") (pintype "passive"))
      (node (ref "X3") (pin "3") (pinfunction "3_3") (pintype "passive"))
    )
    (net (code "71") (name "Net-(R31-left)") (class "Default")
      (node (ref "R31") (pin "1") (pinfunction "left_1") (pintype "passive"))
      (node (ref "X3") (pin "2") (pinfunction "2_2") (pintype "passive"))
    )
    (net (code "72") (name "unconnected-(H1-1-Pad2)") (class "Default")
      (node (ref "H1") (pin "2") (pinfunction "1_2") (pintype "passive"))
    )
    (net (code "73") (name "unconnected-(H1-Pad1)") (class "Default")
      (node (ref "H1") (pin "1") (pinfunction "1_1") (pintype "passive"))
    )
    (net (code "74") (name "unconnected-(H2-1-Pad2)") (class "Default")
      (node (ref "H2") (pin "2") (pinfunction "1_2") (pintype "passive"))
    )
    (net (code "75") (name "unconnected-(H2-Pad1)") (class "Default")
      (node (ref "H2") (pin "1") (pinfunction "1_1") (pintype "passive"))
    )
    (net (code "76") (name "unconnected-(H3-1-Pad2)") (class "Default")
      (node (ref "H3") (pin "2") (pinfunction "1_2") (pintype "passive"))
    )
    (net (code "77") (name "unconnected-(H3-Pad1)") (class "Default")
      (node (ref "H3") (pin "1") (pinfunction "1_1") (pintype "passive"))
    )
    (net (code "78") (name "unconnected-(H4-1-Pad2)") (class "Default")
      (node (ref "H4") (pin "2") (pinfunction "1_2") (pintype "passive"))
    )
    (net (code "79") (name "unconnected-(H4-Pad1)") (class "Default")
      (node (ref "H4") (pin "1") (pinfunction "1_1") (pintype "passive"))
    )
    (net (code "80") (name "unconnected-(H5-Pad1)") (class "Default")
      (node (ref "H5") (pin "1") (pinfunction "1_1") (pintype "passive"))
    )
    (net (code "81") (name "unconnected-(H6-Pad1)") (class "Default")
      (node (ref "H6") (pin "1") (pinfunction "1_1") (pintype "passive"))
    )
    (net (code "82") (name "unconnected-(H7-Pad1)") (class "Default")
      (node (ref "H7") (pin "1") (pinfunction "1_1") (pintype "passive"))
    )
    (net (code "83") (name "unconnected-(H8-Pad1)") (class "Default")
      (node (ref "H8") (pin "1") (pinfunction "1_1") (pintype "passive"))
    )
    (net (code "84") (name "unconnected-(IC8A-pin_2-Pad2)") (class "Default")
      (node (ref "IC8") (pin "2") (pinfunction "pin_2_2") (pintype "passive"))
    )
    (net (code "85") (name "unconnected-(IC8B-pin_2-Pad4)") (class "Default")
      (node (ref "IC8") (pin "4") (pinfunction "pin_2_4") (pintype "passive"))
    )
    (net (code "86") (name "unconnected-(IC9-SDO-Pad7)") (class "Default")
      (node (ref "IC9") (pin "7") (pinfunction "SDO_7") (pintype "passive"))
    )
    (net (code "87") (name "unconnected-(IC10-!AMUTEC-Pad16)") (class "Default")
      (node (ref "IC10") (pin "16") (pinfunction "!AMUTEC_16") (pintype "passive"))
    )
    (net (code "88") (name "unconnected-(IC10-!BMUTEC-Pad21)") (class "Default")
      (node (ref "IC10") (pin "21") (pinfunction "!BMUTEC_21") (pintype "passive"))
    )
    (net (code "89") (name "unconnected-(IC10-TSTO-Pad13)") (class "Default")
      (node (ref "IC10") (pin "13") (pinfunction "TSTO_13") (pintype "passive"))
    )
  )
)
